# deter-board.net
KiCad netlist of a schematic drawn in EAGLE
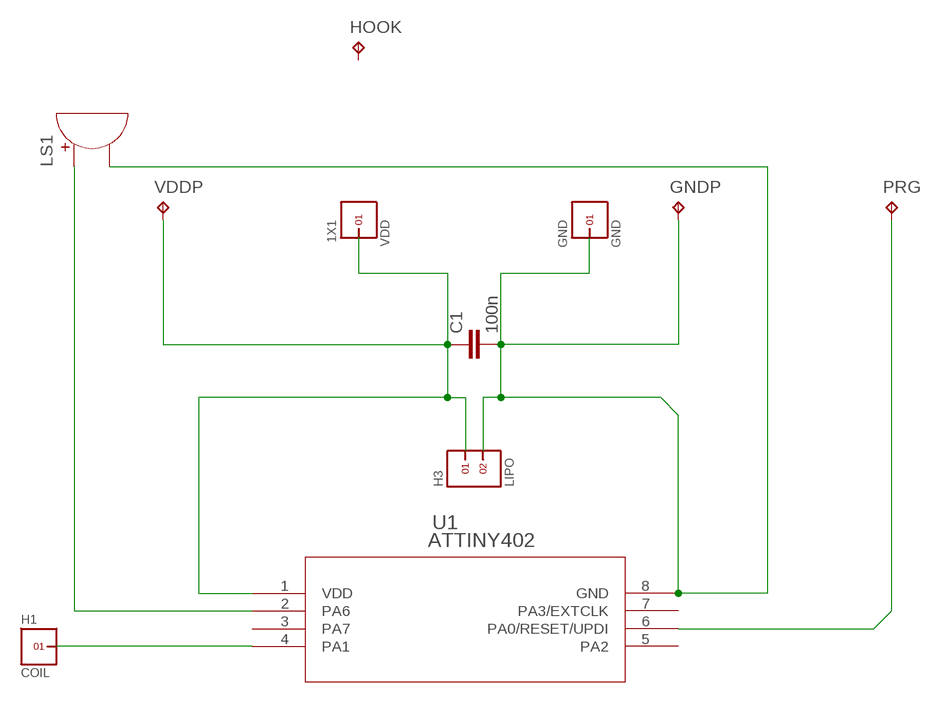
[diagram p0: schematic, sheet 1]

(export (version "E")
  (design (tool "Eeschema 10.0.6"))
  (components
    (comp (ref "C1")
      (value "100n")
      (footprint "eagle-import:1206")
      (libsource (lib "eagle-import") (part "CAP-1206"))
    )
    (comp (ref "GND")
      (value "GND")
      (footprint "eagle-import:1X1")
      (libsource (lib "eagle-import") (part "1X1"))
    )
    (comp (ref "GNDP")
      (value "GND")
      (footprint "eagle-import:B1,27")
      (libsource (lib "eagle-import") (part "TPB1,27"))
    )
    (comp (ref "H1")
      (value "COIL")
      (footprint "eagle-import:1X1")
      (libsource (lib "eagle-import") (part "1X1"))
    )
    (comp (ref "H3")
      (value "LIPO")
      (footprint "eagle-import:1X2")
      (libsource (lib "eagle-import") (part "1X2"))
    )
    (comp (ref "HOOK")
      (value "HOOK")
      (footprint "eagle-import:P1-17Y")
      (libsource (lib "eagle-import") (part "TPPAD1-17Y"))
    )
    (comp (ref "LS1")
      (value "BUZZER_(9650)")
      (footprint "eagle-import:S-BUZZER-MLT-9650")
      (fields (field (name "MPN") "MLT-9650"))
      (libsource (lib "eagle-import") (part "BUZZER_(9650)"))
    )
    (comp (ref "PRG")
      (value "PROG")
      (footprint "eagle-import:B2,54")
      (libsource (lib "eagle-import") (part "TPB2,54"))
    )
    (comp (ref "U1")
      (value "ATTINY402")
      (footprint "eagle-import:SOIC8_4P9X3P9MC_MCH")
      (fields
        (field (name "MANUFACTURER_PART_NUMBER") "ATTINY402-SSN")
        (field (name "COPYRIGHT") "Copyright (C) 2024 Ultra Librarian. All rights reserved.")
      )
      (libsource (lib "eagle-import") (part "ATTINY402-SSN"))
    )
    (comp (ref "VDD")
      (value "1X1")
      (footprint "eagle-import:1X1")
      (libsource (lib "eagle-import") (part "1X1"))
    )
    (comp (ref "VDDP")
      (value "VDD")
      (footprint "eagle-import:B1,27")
      (libsource (lib "eagle-import") (part "TPB1,27"))
    )
  )
  (nets
    (net (code "1") (name "Net-(LS1-+)") (class "Default")
      (node (ref "LS1") (pin "P$2") (pinfunction "+_P$2") (pintype "bidirectional"))
      (node (ref "U1") (pin "2") (pinfunction "PA6_2") (pintype "bidirectional"))
    )
    (net (code "2") (name "Net-(LS1--)") (class "Default")
      (node (ref "C1") (pin "2") (pinfunction "2_2") (pintype "passive"))
      (node (ref "GND") (pin "1") (pinfunction "1_1") (pintype "bidirectional"))
      (node (ref "GNDP") (pin "TP") (pinfunction "TP_TP") (pintype "input"))
      (node (ref "H3") (pin "2") (pinfunction "2_2") (pintype "bidirectional"))
      (node (ref "LS1") (pin "P$1") (pinfunction "-_P$1") (pintype "bidirectional"))
      (node (ref "U1") (pin "8") (pinfunction "GND_8") (pintype "passive"))
    )
    (net (code "3") (name "Net-(U1-PA0{slash}RESET{slash}UPDI)") (class "Default")
      (node (ref "PRG") (pin "TP") (pinfunction "TP_TP") (pintype "input"))
      (node (ref "U1") (pin "6") (pinfunction "PA0/RESET/UPDI_6") (pintype "bidirectional"))
    )
    (net (code "4") (name "Net-(U1-PA1)") (class "Default")
      (node (ref "H1") (pin "1") (pinfunction "1_1") (pintype "bidirectional"))
      (node (ref "U1") (pin "4") (pinfunction "PA1_4") (pintype "bidirectional"))
    )
    (net (code "5") (name "Net-(U1-VDD)") (class "Default")
      (node (ref "C1") (pin "1") (pinfunction "1_1") (pintype "passive"))
      (node (ref "H3") (pin "1") (pinfunction "1_1") (pintype "bidirectional"))
      (node (ref "U1") (pin "1") (pinfunction "VDD_1") (pintype "power_in"))
      (node (ref "VDD") (pin "1") (pinfunction "1_1") (pintype "bidirectional"))
      (node (ref "VDDP") (pin "TP") (pinfunction "TP_TP") (pintype "input"))
    )
    (net (code "6") (name "unconnected-(HOOK-PadTP)") (class "Default")
      (node (ref "HOOK") (pin "TP") (pinfunction "TP_TP") (pintype "input"))
    )
    (net (code "7") (name "unconnected-(U1-PA2-Pad5)") (class "Default")
      (node (ref "U1") (pin "5") (pinfunction "PA2_5") (pintype "bidirectional"))
    )
    (net (code "8") (name "unconnected-(U1-PA3{slash}EXTCLK-Pad7)") (class "Default")
      (node (ref "U1") (pin "7") (pinfunction "PA3/EXTCLK_7") (pintype "bidirectional"))
    )
    (net (code "9") (name "unconnected-(U1-PA7-Pad3)") (class "Default")
      (node (ref "U1") (pin "3") (pinfunction "PA7_3") (pintype "bidirectional"))
    )
  )
)
